# VNH7070AS_test_PCB.net
KiCad netlist of a schematic drawn in EAGLE
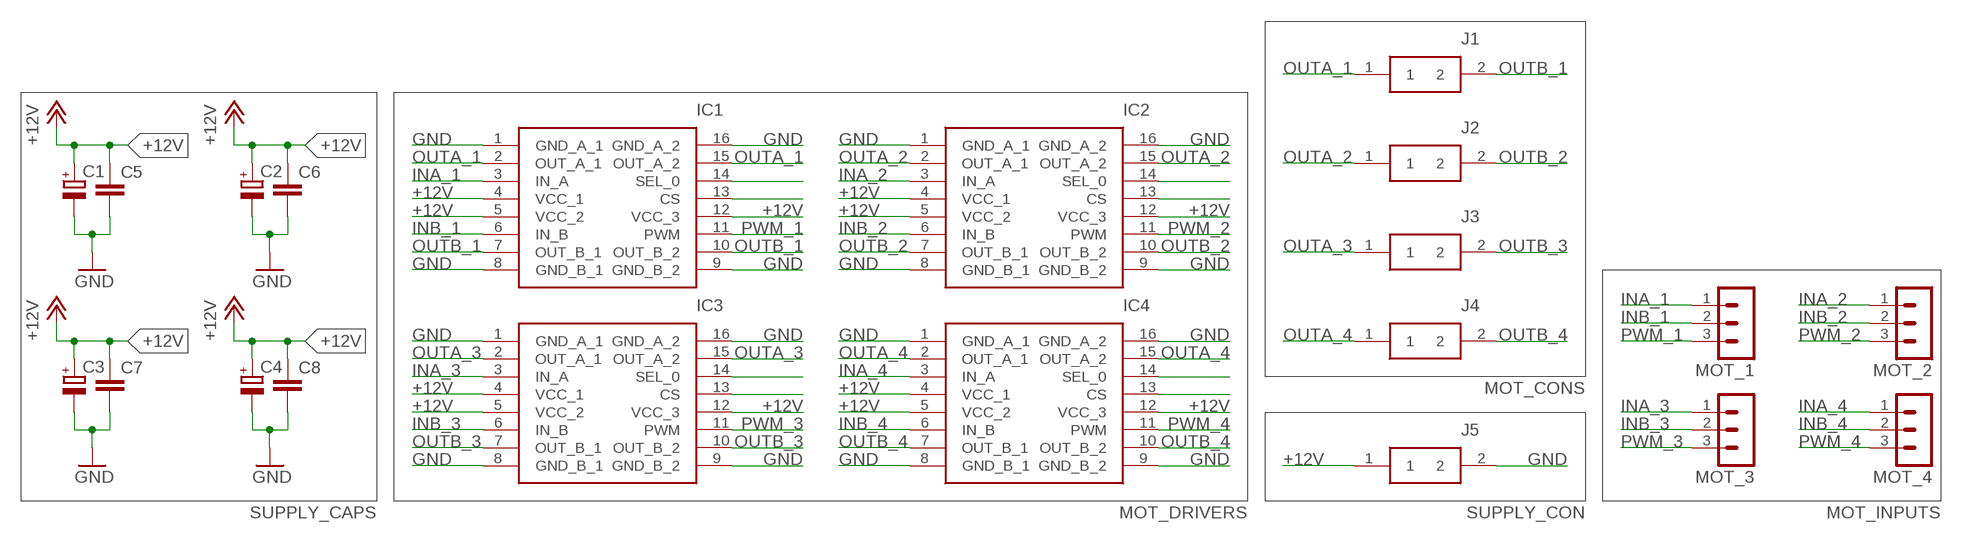
[diagram p0: schematic, sheet 1]

(export (version "E")
  (design (tool "Eeschema 10.0.6"))
  (components
    (comp (ref "C1")
      (value "220uF")
      (footprint "eagle-import:E3,5-8")
      (libsource (lib "eagle-import") (part "CPOL-EUE3.5-8"))
    )
    (comp (ref "C2")
      (value "220uF")
      (footprint "eagle-import:E3,5-8")
      (libsource (lib "eagle-import") (part "CPOL-EUE3.5-8"))
    )
    (comp (ref "C3")
      (value "220uF")
      (footprint "eagle-import:E3,5-8")
      (libsource (lib "eagle-import") (part "CPOL-EUE3.5-8"))
    )
    (comp (ref "C4")
      (value "220uF")
      (footprint "eagle-import:E3,5-8")
      (libsource (lib "eagle-import") (part "CPOL-EUE3.5-8"))
    )
    (comp (ref "C5")
      (value "100nF")
      (footprint "eagle-import:C1206")
      (libsource (lib "eagle-import") (part "C-EUC1206"))
    )
    (comp (ref "C6")
      (value "100nF")
      (footprint "eagle-import:C1206")
      (libsource (lib "eagle-import") (part "C-EUC1206"))
    )
    (comp (ref "C7")
      (value "100nF")
      (footprint "eagle-import:C1206")
      (libsource (lib "eagle-import") (part "C-EUC1206"))
    )
    (comp (ref "C8")
      (value "100nF")
      (footprint "eagle-import:C1206")
      (libsource (lib "eagle-import") (part "C-EUC1206"))
    )
    (comp (ref "IC1")
      (value "VNH7070ASTR")
      (footprint "eagle-import:SOIC127P600X175-16N")
      (fields
        (field (name "MOUSER_PART_NUMBER") "511-VNH7070ASTR")
        (field (name "RS_PART_NUMBER") "1647017P")
      )
      (libsource (lib "eagle-import") (part "VNH7070ASTR"))
    )
    (comp (ref "IC2")
      (value "VNH7070ASTR")
      (footprint "eagle-import:SOIC127P600X175-16N")
      (fields
        (field (name "MOUSER_PART_NUMBER") "511-VNH7070ASTR")
        (field (name "RS_PART_NUMBER") "1647017P")
      )
      (libsource (lib "eagle-import") (part "VNH7070ASTR"))
    )
    (comp (ref "IC3")
      (value "VNH7070ASTR")
      (footprint "eagle-import:SOIC127P600X175-16N")
      (fields
        (field (name "MOUSER_PART_NUMBER") "511-VNH7070ASTR")
        (field (name "RS_PART_NUMBER") "1647017P")
      )
      (libsource (lib "eagle-import") (part "VNH7070ASTR"))
    )
    (comp (ref "IC4")
      (value "VNH7070ASTR")
      (footprint "eagle-import:SOIC127P600X175-16N")
      (fields
        (field (name "MOUSER_PART_NUMBER") "511-VNH7070ASTR")
        (field (name "RS_PART_NUMBER") "1647017P")
      )
      (libsource (lib "eagle-import") (part "VNH7070ASTR"))
    )
    (comp (ref "J1")
      (value "70553-0001")
      (footprint "eagle-import:SHDRRA2W109P0_254_1X2_762X1359")
      (fields (field (name "MOUSER_PART_NUMBER") "538-70553-0001") (field (name "RS_PART_NUMBER") "6792516P"))
      (libsource (lib "eagle-import") (part "70553-0001"))
    )
    (comp (ref "J2")
      (value "70553-0001")
      (footprint "eagle-import:SHDRRA2W109P0_254_1X2_762X1359")
      (fields (field (name "MOUSER_PART_NUMBER") "538-70553-0001") (field (name "RS_PART_NUMBER") "6792516P"))
      (libsource (lib "eagle-import") (part "70553-0001"))
    )
    (comp (ref "J3")
      (value "70553-0001")
      (footprint "eagle-import:SHDRRA2W109P0_254_1X2_762X1359")
      (fields (field (name "MOUSER_PART_NUMBER") "538-70553-0001") (field (name "RS_PART_NUMBER") "6792516P"))
      (libsource (lib "eagle-import") (part "70553-0001"))
    )
    (comp (ref "J4")
      (value "70553-0001")
      (footprint "eagle-import:SHDRRA2W109P0_254_1X2_762X1359")
      (fields (field (name "MOUSER_PART_NUMBER") "538-70553-0001") (field (name "RS_PART_NUMBER") "6792516P"))
      (libsource (lib "eagle-import") (part "70553-0001"))
    )
    (comp (ref "J5")
      (value "70553-0001")
      (footprint "eagle-import:SHDRRA2W109P0_254_1X2_762X1359")
      (fields (field (name "MOUSER_PART_NUMBER") "538-70553-0001") (field (name "RS_PART_NUMBER") "6792516P"))
      (libsource (lib "eagle-import") (part "70553-0001"))
    )
    (comp (ref "MOT_1")
      (value "MA03-1")
      (footprint "eagle-import:MA03-1")
      (libsource (lib "eagle-import") (part "MA03-1"))
    )
    (comp (ref "MOT_2")
      (value "MA03-1")
      (footprint "eagle-import:MA03-1")
      (libsource (lib "eagle-import") (part "MA03-1"))
    )
    (comp (ref "MOT_3")
      (value "MA03-1")
      (footprint "eagle-import:MA03-1")
      (libsource (lib "eagle-import") (part "MA03-1"))
    )
    (comp (ref "MOT_4")
      (value "MA03-1")
      (footprint "eagle-import:MA03-1")
      (libsource (lib "eagle-import") (part "MA03-1"))
    )
  )
  (nets
    (net (code "1") (name "+12V") (class "Default")
      (node (ref "C1") (pin "+") (pinfunction "+_+") (pintype "passive"))
      (node (ref "C2") (pin "+") (pinfunction "+_+") (pintype "passive"))
      (node (ref "C3") (pin "+") (pinfunction "+_+") (pintype "passive"))
      (node (ref "C4") (pin "+") (pinfunction "+_+") (pintype "passive"))
      (node (ref "C5") (pin "1") (pinfunction "1_1") (pintype "passive"))
      (node (ref "C6") (pin "1") (pinfunction "1_1") (pintype "passive"))
      (node (ref "C7") (pin "1") (pinfunction "1_1") (pintype "passive"))
      (node (ref "C8") (pin "1") (pinfunction "1_1") (pintype "passive"))
      (node (ref "IC1") (pin "12") (pinfunction "VCC_3_12") (pintype "bidirectional"))
      (node (ref "IC1") (pin "4") (pinfunction "VCC_1_4") (pintype "bidirectional"))
      (node (ref "IC1") (pin "5") (pinfunction "VCC_2_5") (pintype "bidirectional"))
      (node (ref "IC2") (pin "12") (pinfunction "VCC_3_12") (pintype "bidirectional"))
      (node (ref "IC2") (pin "4") (pinfunction "VCC_1_4") (pintype "bidirectional"))
      (node (ref "IC2") (pin "5") (pinfunction "VCC_2_5") (pintype "bidirectional"))
      (node (ref "IC3") (pin "12") (pinfunction "VCC_3_12") (pintype "bidirectional"))
      (node (ref "IC3") (pin "4") (pinfunction "VCC_1_4") (pintype "bidirectional"))
      (node (ref "IC3") (pin "5") (pinfunction "VCC_2_5") (pintype "bidirectional"))
      (node (ref "IC4") (pin "12") (pinfunction "VCC_3_12") (pintype "bidirectional"))
      (node (ref "IC4") (pin "4") (pinfunction "VCC_1_4") (pintype "bidirectional"))
      (node (ref "IC4") (pin "5") (pinfunction "VCC_2_5") (pintype "bidirectional"))
      (node (ref "J5") (pin "1") (pinfunction "1_1") (pintype "bidirectional"))
    )
    (net (code "2") (name "/INA_1") (class "Default")
      (node (ref "IC1") (pin "3") (pinfunction "IN_A_3") (pintype "bidirectional"))
      (node (ref "MOT_1") (pin "1") (pinfunction "1_1") (pintype "passive"))
    )
    (net (code "3") (name "/INA_2") (class "Default")
      (node (ref "IC2") (pin "3") (pinfunction "IN_A_3") (pintype "bidirectional"))
      (node (ref "MOT_2") (pin "1") (pinfunction "1_1") (pintype "passive"))
    )
    (net (code "4") (name "/INA_3") (class "Default")
      (node (ref "IC3") (pin "3") (pinfunction "IN_A_3") (pintype "bidirectional"))
      (node (ref "MOT_3") (pin "1") (pinfunction "1_1") (pintype "passive"))
    )
    (net (code "5") (name "/INA_4") (class "Default")
      (node (ref "IC4") (pin "3") (pinfunction "IN_A_3") (pintype "bidirectional"))
      (node (ref "MOT_4") (pin "1") (pinfunction "1_1") (pintype "passive"))
    )
    (net (code "6") (name "/INB_1") (class "Default")
      (node (ref "IC1") (pin "6") (pinfunction "IN_B_6") (pintype "bidirectional"))
      (node (ref "MOT_1") (pin "2") (pinfunction "2_2") (pintype "passive"))
    )
    (net (code "7") (name "/INB_2") (class "Default")
      (node (ref "IC2") (pin "6") (pinfunction "IN_B_6") (pintype "bidirectional"))
      (node (ref "MOT_2") (pin "2") (pinfunction "2_2") (pintype "passive"))
    )
    (net (code "8") (name "/INB_3") (class "Default")
      (node (ref "IC3") (pin "6") (pinfunction "IN_B_6") (pintype "bidirectional"))
      (node (ref "MOT_3") (pin "2") (pinfunction "2_2") (pintype "passive"))
    )
    (net (code "9") (name "/INB_4") (class "Default")
      (node (ref "IC4") (pin "6") (pinfunction "IN_B_6") (pintype "bidirectional"))
      (node (ref "MOT_4") (pin "2") (pinfunction "2_2") (pintype "passive"))
    )
    (net (code "10") (name "/OUTA_1") (class "Default")
      (node (ref "IC1") (pin "15") (pinfunction "OUT_A_2_15") (pintype "bidirectional"))
      (node (ref "IC1") (pin "2") (pinfunction "OUT_A_1_2") (pintype "bidirectional"))
      (node (ref "J1") (pin "1") (pinfunction "1_1") (pintype "bidirectional"))
    )
    (net (code "11") (name "/OUTA_2") (class "Default")
      (node (ref "IC2") (pin "15") (pinfunction "OUT_A_2_15") (pintype "bidirectional"))
      (node (ref "IC2") (pin "2") (pinfunction "OUT_A_1_2") (pintype "bidirectional"))
      (node (ref "J2") (pin "1") (pinfunction "1_1") (pintype "bidirectional"))
    )
    (net (code "12") (name "/OUTA_3") (class "Default")
      (node (ref "IC3") (pin "15") (pinfunction "OUT_A_2_15") (pintype "bidirectional"))
      (node (ref "IC3") (pin "2") (pinfunction "OUT_A_1_2") (pintype "bidirectional"))
      (node (ref "J3") (pin "1") (pinfunction "1_1") (pintype "bidirectional"))
    )
    (net (code "13") (name "/OUTA_4") (class "Default")
      (node (ref "IC4") (pin "15") (pinfunction "OUT_A_2_15") (pintype "bidirectional"))
      (node (ref "IC4") (pin "2") (pinfunction "OUT_A_1_2") (pintype "bidirectional"))
      (node (ref "J4") (pin "1") (pinfunction "1_1") (pintype "bidirectional"))
    )
    (net (code "14") (name "/OUTB_1") (class "Default")
      (node (ref "IC1") (pin "10") (pinfunction "OUT_B_2_10") (pintype "bidirectional"))
      (node (ref "IC1") (pin "7") (pinfunction "OUT_B_1_7") (pintype "bidirectional"))
      (node (ref "J1") (pin "2") (pinfunction "2_2") (pintype "bidirectional"))
    )
    (net (code "15") (name "/OUTB_2") (class "Default")
      (node (ref "IC2") (pin "10") (pinfunction "OUT_B_2_10") (pintype "bidirectional"))
      (node (ref "IC2") (pin "7") (pinfunction "OUT_B_1_7") (pintype "bidirectional"))
      (node (ref "J2") (pin "2") (pinfunction "2_2") (pintype "bidirectional"))
    )
    (net (code "16") (name "/OUTB_3") (class "Default")
      (node (ref "IC3") (pin "10") (pinfunction "OUT_B_2_10") (pintype "bidirectional"))
      (node (ref "IC3") (pin "7") (pinfunction "OUT_B_1_7") (pintype "bidirectional"))
      (node (ref "J3") (pin "2") (pinfunction "2_2") (pintype "bidirectional"))
    )
    (net (code "17") (name "/OUTB_4") (class "Default")
      (node (ref "IC4") (pin "10") (pinfunction "OUT_B_2_10") (pintype "bidirectional"))
      (node (ref "IC4") (pin "7") (pinfunction "OUT_B_1_7") (pintype "bidirectional"))
      (node (ref "J4") (pin "2") (pinfunction "2_2") (pintype "bidirectional"))
    )
    (net (code "18") (name "/PWM_1") (class "Default")
      (node (ref "IC1") (pin "11") (pinfunction "PWM_11") (pintype "bidirectional"))
      (node (ref "MOT_1") (pin "3") (pinfunction "3_3") (pintype "passive"))
    )
    (net (code "19") (name "/PWM_2") (class "Default")
      (node (ref "IC2") (pin "11") (pinfunction "PWM_11") (pintype "bidirectional"))
      (node (ref "MOT_2") (pin "3") (pinfunction "3_3") (pintype "passive"))
    )
    (net (code "20") (name "/PWM_3") (class "Default")
      (node (ref "IC3") (pin "11") (pinfunction "PWM_11") (pintype "bidirectional"))
      (node (ref "MOT_3") (pin "3") (pinfunction "3_3") (pintype "passive"))
    )
    (net (code "21") (name "/PWM_4") (class "Default")
      (node (ref "IC4") (pin "11") (pinfunction "PWM_11") (pintype "bidirectional"))
      (node (ref "MOT_4") (pin "3") (pinfunction "3_3") (pintype "passive"))
    )
    (net (code "22") (name "GND") (class "Default")
      (node (ref "C1") (pin "-") (pinfunction "-_-") (pintype "passive"))
      (node (ref "C2") (pin "-") (pinfunction "-_-") (pintype "passive"))
      (node (ref "C3") (pin "-") (pinfunction "-_-") (pintype "passive"))
      (node (ref "C4") (pin "-") (pinfunction "-_-") (pintype "passive"))
      (node (ref "C5") (pin "2") (pinfunction "2_2") (pintype "passive"))
      (node (ref "C6") (pin "2") (pinfunction "2_2") (pintype "passive"))
      (node (ref "C7") (pin "2") (pinfunction "2_2") (pintype "passive"))
      (node (ref "C8") (pin "2") (pinfunction "2_2") (pintype "passive"))
      (node (ref "IC1") (pin "1") (pinfunction "GND_A_1_1") (pintype "bidirectional"))
      (node (ref "IC1") (pin "16") (pinfunction "GND_A_2_16") (pintype "bidirectional"))
      (node (ref "IC1") (pin "8") (pinfunction "GND_B_1_8") (pintype "bidirectional"))
      (node (ref "IC1") (pin "9") (pinfunction "GND_B_2_9") (pintype "bidirectional"))
      (node (ref "IC2") (pin "1") (pinfunction "GND_A_1_1") (pintype "bidirectional"))
      (node (ref "IC2") (pin "16") (pinfunction "GND_A_2_16") (pintype "bidirectional"))
      (node (ref "IC2") (pin "8") (pinfunction "GND_B_1_8") (pintype "bidirectional"))
      (node (ref "IC2") (pin "9") (pinfunction "GND_B_2_9") (pintype "bidirectional"))
      (node (ref "IC3") (pin "1") (pinfunction "GND_A_1_1") (pintype "bidirectional"))
      (node (ref "IC3") (pin "16") (pinfunction "GND_A_2_16") (pintype "bidirectional"))
      (node (ref "IC3") (pin "8") (pinfunction "GND_B_1_8") (pintype "bidirectional"))
      (node (ref "IC3") (pin "9") (pinfunction "GND_B_2_9") (pintype "bidirectional"))
      (node (ref "IC4") (pin "1") (pinfunction "GND_A_1_1") (pintype "bidirectional"))
      (node (ref "IC4") (pin "16") (pinfunction "GND_A_2_16") (pintype "bidirectional"))
      (node (ref "IC4") (pin "8") (pinfunction "GND_B_1_8") (pintype "bidirectional"))
      (node (ref "IC4") (pin "9") (pinfunction "GND_B_2_9") (pintype "bidirectional"))
      (node (ref "J5") (pin "2") (pinfunction "2_2") (pintype "bidirectional"))
    )
    (net (code "23") (name "unconnected-(IC1-CS-Pad13)") (class "Default")
      (node (ref "IC1") (pin "13") (pinfunction "CS_13") (pintype "bidirectional"))
    )
    (net (code "24") (name "unconnected-(IC1-SEL_0-Pad14)") (class "Default")
      (node (ref "IC1") (pin "14") (pinfunction "SEL_0_14") (pintype "bidirectional"))
    )
    (net (code "25") (name "unconnected-(IC2-CS-Pad13)") (class "Default")
      (node (ref "IC2") (pin "13") (pinfunction "CS_13") (pintype "bidirectional"))
    )
    (net (code "26") (name "unconnected-(IC2-SEL_0-Pad14)") (class "Default")
      (node (ref "IC2") (pin "14") (pinfunction "SEL_0_14") (pintype "bidirectional"))
    )
    (net (code "27") (name "unconnected-(IC3-CS-Pad13)") (class "Default")
      (node (ref "IC3") (pin "13") (pinfunction "CS_13") (pintype "bidirectional"))
    )
    (net (code "28") (name "unconnected-(IC3-SEL_0-Pad14)") (class "Default")
      (node (ref "IC3") (pin "14") (pinfunction "SEL_0_14") (pintype "bidirectional"))
    )
    (net (code "29") (name "unconnected-(IC4-CS-Pad13)") (class "Default")
      (node (ref "IC4") (pin "13") (pinfunction "CS_13") (pintype "bidirectional"))
    )
    (net (code "30") (name "unconnected-(IC4-SEL_0-Pad14)") (class "Default")
      (node (ref "IC4") (pin "14") (pinfunction "SEL_0_14") (pintype "bidirectional"))
    )
  )
)
